# MB1280.net
KiCad netlist of a schematic drawn in Altium Designer
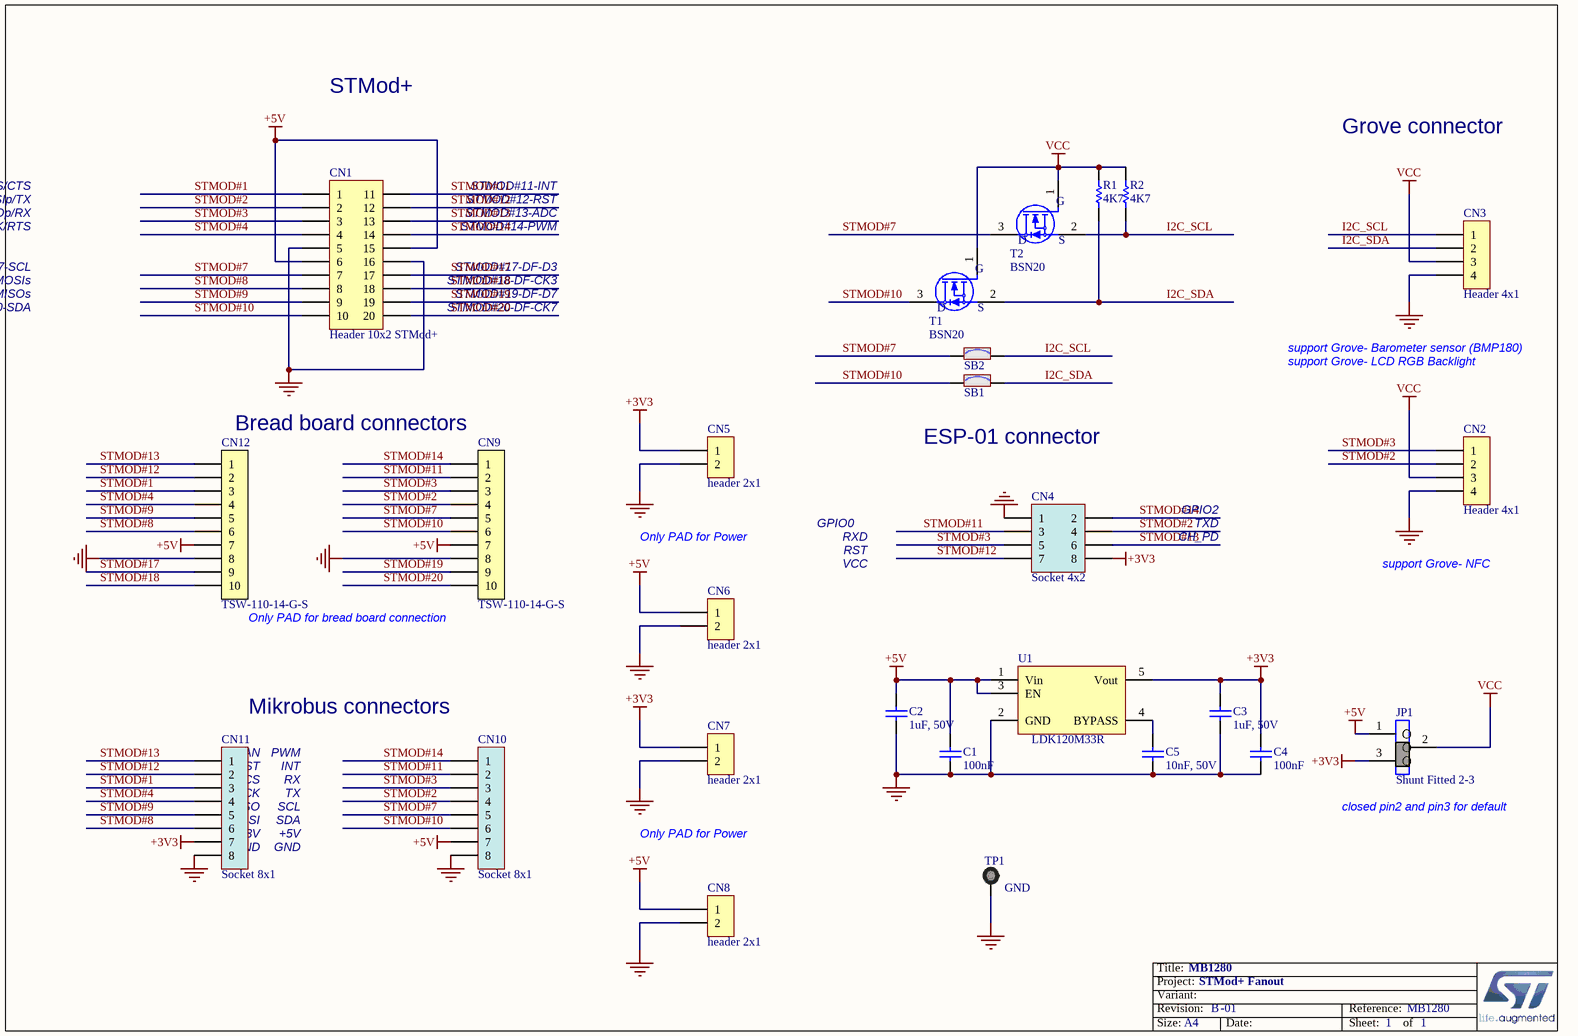
[diagram p0: MB1280.SchDoc]

(export (version "E")
  (design (tool "Eeschema 10.0.6"))
  (components
    (comp (ref "C1")
      (value "100nF")
      (footprint "C0603")
      (description "Capacitor, MLCC, 100nF, 16V, X7R, 10%, 0603, T=0,8mm")
      (fields
        (field (name "INTERNAL_PART_NUMBER") "MCD-00211")
        (field (name "MANUFACTURER_PART_NUMBER") "CC0603KRX7R7BB104")
        (field (name "PROVIDED_BY") "SUBCO")
      )
      (libsource (lib "MCD_PARTS_database") (part "Capacitor"))
    )
    (comp (ref "C2")
      (value "1uF, 50V")
      (footprint "C0603_H0P8")
      (description "Capacitor,1uF,50V,X5R,10%,0603, T=0.8mm")
      (fields
        (field (name "INTERNAL_PART_NUMBER") "MCD-01703")
        (field (name "MANUFACTURER_PART_NUMBER") "CC0603KRX5R9BB105")
        (field (name "PROVIDED_BY") "SUBCO")
      )
      (libsource (lib "MCD_PARTS_database") (part "Capacitor"))
    )
    (comp (ref "C3")
      (value "1uF, 50V")
      (footprint "C0603_H0P8")
      (description "Capacitor,1uF,50V,X5R,10%,0603, T=0.8mm")
      (fields
        (field (name "INTERNAL_PART_NUMBER") "MCD-01703")
        (field (name "MANUFACTURER_PART_NUMBER") "CC0603KRX5R9BB105")
        (field (name "PROVIDED_BY") "SUBCO")
      )
      (libsource (lib "MCD_PARTS_database") (part "Capacitor"))
    )
    (comp (ref "C4")
      (value "100nF")
      (footprint "C0603")
      (description "Capacitor, MLCC, 100nF, 16V, X7R, 10%, 0603, T=0,8mm")
      (fields
        (field (name "INTERNAL_PART_NUMBER") "MCD-00211")
        (field (name "MANUFACTURER_PART_NUMBER") "CC0603KRX7R7BB104")
        (field (name "PROVIDED_BY") "SUBCO")
      )
      (libsource (lib "MCD_PARTS_database") (part "Capacitor"))
    )
    (comp (ref "C5")
      (value "10nF, 50V")
      (footprint "C0603")
      (description "Capacitor,10nF,50V,X7R,10%,0603")
      (fields
        (field (name "INTERNAL_PART_NUMBER") "MCD-01102")
        (field (name "MANUFACTURER_PART_NUMBER") "CC0603KRX7R9BB103")
        (field (name "PROVIDED_BY") "SUBCO")
      )
      (libsource (lib "MCD_PARTS_database") (part "Capacitor"))
    )
    (comp (ref "CN1")
      (value "Header 10x2 STMod+")
      (footprint "CON_SAMTEC_TMM-110-01-L-D-RA__STMOD+")
      (description "Header 10x2, 2mm, RA, TH, Height 3.20mm/3.50mm")
      (fields
        (field (name "INTERNAL_PART_NUMBER") "MCD-00288")
        (field (name "MANUFACTURER_PART_NUMBER") "TMM-110-01-L-D-RA")
        (field (name "PROVIDED_BY") "SUBCO")
      )
      (libsource (lib "MCD_PARTS_database") (part "Header 10x2 STMod+"))
    )
    (comp (ref "CN2")
      (value "Header 4x1")
      (footprint "CON_988-JIUBABA_A2006LF-04A")
      (description "Header 4x1, 2mm, VR, SMT")
      (fields
        (field (name "INTERNAL_PART_NUMBER") "MCD-01741")
        (field (name "MANUFACTURER_PART_NUMBER") "A2006LF-04A")
        (field (name "PROVIDED_BY") "SUBCO")
      )
      (libsource (lib "MCD_PARTS_database") (part "Header 4x1"))
    )
    (comp (ref "CN3")
      (value "Header 4x1")
      (footprint "CON_988-JIUBABA_A2006LF-04A")
      (description "Header 4x1, 2mm, VR, SMT")
      (fields
        (field (name "INTERNAL_PART_NUMBER") "MCD-01741")
        (field (name "MANUFACTURER_PART_NUMBER") "A2006LF-04A")
        (field (name "PROVIDED_BY") "SUBCO")
      )
      (libsource (lib "MCD_PARTS_database") (part "Header 4x1"))
    )
    (comp (ref "CN4")
      (value "Socket 4x2")
      (footprint "CON_SAMTEC_SSW-104-01-X-D")
      (description "Socket 4x2,2.54mm,VR,TH, height 8.51/2.64mm")
      (fields
        (field (name "INTERNAL_PART_NUMBER") "MCD-01742")
        (field (name "MANUFACTURER_PART_NUMBER") "SSW-104-01-G-D")
        (field (name "PROVIDED_BY") "SUBCO")
      )
      (libsource (lib "MCD_PARTS_database") (part "Socket 4x2"))
    )
    (comp (ref "CN5")
      (value "header 2x1")
      (footprint "CON_988-JIUBABA_PHFS25-11-02-G0B115-T-1")
      (description "Header, 2x1, 2.54mm, VR, TH, Height 6mm/3mm")
      (fields
        (field (name "INTERNAL_PART_NUMBER") "MCD-00314")
        (field (name "MANUFACTURER_PART_NUMBER") "PHFS25-11-02-G0B115-T-1")
        (field (name "PROVIDED_BY") "SUBCO")
      )
      (libsource (lib "MCD_PARTS_database") (part "Header 2x1"))
    )
    (comp (ref "CN6")
      (value "header 2x1")
      (footprint "CON_988-JIUBABA_PHFS25-11-02-G0B115-T-1")
      (description "Header, 2x1, 2.54mm, VR, TH, Height 6mm/3mm")
      (fields
        (field (name "INTERNAL_PART_NUMBER") "MCD-00314")
        (field (name "MANUFACTURER_PART_NUMBER") "PHFS25-11-02-G0B115-T-1")
        (field (name "PROVIDED_BY") "SUBCO")
      )
      (libsource (lib "MCD_PARTS_database") (part "Header 2x1"))
    )
    (comp (ref "CN7")
      (value "header 2x1")
      (footprint "CON_988-JIUBABA_PHFS25-11-02-G0B115-T-1")
      (description "Header, 2x1, 2.54mm, VR, TH, Height 6mm/3mm")
      (fields
        (field (name "INTERNAL_PART_NUMBER") "MCD-00314")
        (field (name "MANUFACTURER_PART_NUMBER") "PHFS25-11-02-G0B115-T-1")
        (field (name "PROVIDED_BY") "SUBCO")
      )
      (libsource (lib "MCD_PARTS_database") (part "Header 2x1"))
    )
    (comp (ref "CN8")
      (value "header 2x1")
      (footprint "CON_988-JIUBABA_PHFS25-11-02-G0B115-T-1")
      (description "Header, 2x1, 2.54mm, VR, TH, Height 6mm/3mm")
      (fields
        (field (name "INTERNAL_PART_NUMBER") "MCD-00314")
        (field (name "MANUFACTURER_PART_NUMBER") "PHFS25-11-02-G0B115-T-1")
        (field (name "PROVIDED_BY") "SUBCO")
      )
      (libsource (lib "MCD_PARTS_database") (part "Header 2x1"))
    )
    (comp (ref "CN9")
      (value "TSW-110-14-G-S")
      (footprint "CON_SAMTEC_TSW-110-14-G-S")
      (description "Header 10x1, 2,54mm height  10.67mm")
      (fields
        (field (name "INTERNAL_PART_NUMBER") "MCD-01591")
        (field (name "MANUFACTURER") "SAMTEC")
        (field (name "PROVIDED_BY") "SUBCO")
      )
      (libsource (lib "MCD_PARTS_database") (part "Header 10x1"))
    )
    (comp (ref "CN10")
      (value "Socket 8x1")
      (footprint "CON_SAMTEC_SSW-108-01-X-S")
      (description "Socket 8x1, 2.54mm, VR, TH, height 8.51/2.64mm")
      (fields
        (field (name "INTERNAL_PART_NUMBER") "MCD-01743")
        (field (name "MANUFACTURER_PART_NUMBER") "SSW-108-01-x-S")
        (field (name "PROVIDED_BY") "SUBCO")
      )
      (libsource (lib "MCD_PARTS_database") (part "Socket 8x1"))
    )
    (comp (ref "CN11")
      (value "Socket 8x1")
      (footprint "CON_SAMTEC_SSW-108-01-X-S")
      (description "Socket 8x1, 2.54mm, VR, TH, height 8.51/2.64mm")
      (fields
        (field (name "INTERNAL_PART_NUMBER") "MCD-01743")
        (field (name "MANUFACTURER_PART_NUMBER") "SSW-108-01-x-S")
        (field (name "PROVIDED_BY") "SUBCO")
      )
      (libsource (lib "MCD_PARTS_database") (part "Socket 8x1"))
    )
    (comp (ref "CN12")
      (value "TSW-110-14-G-S")
      (footprint "CON_SAMTEC_TSW-110-14-G-S")
      (description "Header 10x1, 2,54mm height  10.67mm")
      (fields
        (field (name "INTERNAL_PART_NUMBER") "MCD-01591")
        (field (name "MANUFACTURER") "SAMTEC")
        (field (name "PROVIDED_BY") "SUBCO")
      )
      (libsource (lib "MCD_PARTS_database") (part "Header 10x1"))
    )
    (comp (ref "JP1")
      (value "Shunt Fitted 2-3")
      (footprint "CON_SAMTEC_TSW-103-07-F-S")
      (description "Header, 3x1, 2,54mm, VR, TH, Height 5.84mm/2.54mm - Shunt Fitted 2-3 by default")
      (fields
        (field (name "INTERNAL_PART_NUMBER") "MCD-00685")
        (field (name "MANUFACTURER_PART_NUMBER") "TSW-103-07-F-S")
        (field (name "PROVIDED_BY") "SUBCO")
      )
      (libsource (lib "MCD_PARTS_database") (part "Jumper_Header 3x1 Fitted 2-3"))
    )
    (comp (ref "R1")
      (value "4K7")
      (footprint "R0603")
      (description "Resistor,4K7,0603,1%,1/10W")
      (fields
        (field (name "INTERNAL_PART_NUMBER") "MCD-00219")
        (field (name "MANUFACTURER_PART_NUMBER") "RC0603FR-074K7L")
        (field (name "PROVIDED_BY") "SUBCO")
      )
      (libsource (lib "MCD_PARTS_database") (part "Resistor"))
    )
    (comp (ref "R2")
      (value "4K7")
      (footprint "R0603")
      (description "Resistor,4K7,0603,1%,1/10W")
      (fields
        (field (name "INTERNAL_PART_NUMBER") "MCD-00219")
        (field (name "MANUFACTURER_PART_NUMBER") "RC0603FR-074K7L")
        (field (name "PROVIDED_BY") "SUBCO")
      )
      (libsource (lib "MCD_PARTS_database") (part "Resistor"))
    )
    (comp (ref "SB1")
      (value "SB_ON")
      (footprint "SOLDER-BRIDGE_R0603-0R")
      (description "Solder Bridge ON")
      (fields
        (field (name "INTERNAL_PART_NUMBER") "MCD-00071")
        (field (name "MANUFACTURER_PART_NUMBER") "RC0603JR-070RL")
        (field (name "PROVIDED_BY") "SUBCO")
      )
      (libsource (lib "MCD_PARTS_database") (part "SB_ON"))
    )
    (comp (ref "SB2")
      (value "SB_ON")
      (footprint "SOLDER-BRIDGE_R0603-0R")
      (description "Solder Bridge ON")
      (fields
        (field (name "INTERNAL_PART_NUMBER") "MCD-00071")
        (field (name "MANUFACTURER_PART_NUMBER") "RC0603JR-070RL")
        (field (name "PROVIDED_BY") "SUBCO")
      )
      (libsource (lib "MCD_PARTS_database") (part "SB_ON"))
    )
    (comp (ref "T1")
      (value "BSN20")
      (footprint "MOS_SOT23")
      (description "N-channel enhancement mode field-effect transistor")
      (fields
        (field (name "INTERNAL_PART_NUMBER") "MCD-00151")
        (field (name "MANUFACTURER") "NXP")
        (field (name "PROVIDED_BY") "SUBCO")
      )
      (libsource (lib "MCD_PARTS_database") (part "BSN20"))
    )
    (comp (ref "T2")
      (value "BSN20")
      (footprint "MOS_SOT23")
      (description "N-channel enhancement mode field-effect transistor")
      (fields
        (field (name "INTERNAL_PART_NUMBER") "MCD-00151")
        (field (name "MANUFACTURER") "NXP")
        (field (name "PROVIDED_BY") "SUBCO")
      )
      (libsource (lib "MCD_PARTS_database") (part "BSN20"))
    )
    (comp (ref "TP1")
      (value "GND")
      (footprint "TP_PTH_1MM_2MM")
      (description "Test Point trought hole 1mm/2mm")
      (fields
        (field (name "INTERNAL_PART_NUMBER") "MCD-01506")
        (field (name "MANUFACTURER_PART_NUMBER") "n/a")
      )
      (libsource (lib "MCD_PARTS_database") (part "Test_Point_PTH_1mm_2mm"))
    )
    (comp (ref "U1")
      (value "LDK120M33R")
      (footprint "REG_SOT23-5L")
      (description "200 mA low quiescent current very low noise LDO")
      (fields
        (field (name "INTERNAL_PART_NUMBER") "MCD-00663")
        (field (name "MANUFACTURER") "STMICROELECTRONICS")
        (field (name "PROVIDED_BY") "SUBCO with ST control")
      )
      (libsource (lib "MCD_PARTS_database") (part "LDK120M33R"))
    )
  )
  (nets
    (net (code "1") (name "+3V3") (class "Default")
      (node (ref "C3") (pin "2") (pinfunction "2_2") (pintype "passive"))
      (node (ref "C4") (pin "2") (pinfunction "2_2") (pintype "passive"))
      (node (ref "CN11") (pin "7") (pinfunction "7_7") (pintype "passive"))
      (node (ref "CN4") (pin "8") (pinfunction "8_8") (pintype "passive"))
      (node (ref "CN5") (pin "1") (pinfunction "1_1") (pintype "passive"))
      (node (ref "CN7") (pin "1") (pinfunction "1_1") (pintype "passive"))
      (node (ref "JP1") (pin "3") (pinfunction "3_3") (pintype "passive"))
      (node (ref "U1") (pin "5") (pinfunction "Vout_5") (pintype "power_in"))
    )
    (net (code "2") (name "+5V") (class "Default")
      (node (ref "C1") (pin "2") (pinfunction "2_2") (pintype "passive"))
      (node (ref "C2") (pin "2") (pinfunction "2_2") (pintype "passive"))
      (node (ref "CN1") (pin "15") (pinfunction "15_15") (pintype "passive"))
      (node (ref "CN1") (pin "6") (pinfunction "6_6") (pintype "passive"))
      (node (ref "CN10") (pin "7") (pinfunction "7_7") (pintype "passive"))
      (node (ref "CN12") (pin "7") (pinfunction "7_7") (pintype "passive"))
      (node (ref "CN6") (pin "1") (pinfunction "1_1") (pintype "passive"))
      (node (ref "CN8") (pin "1") (pinfunction "1_1") (pintype "passive"))
      (node (ref "CN9") (pin "7") (pinfunction "7_7") (pintype "passive"))
      (node (ref "JP1") (pin "1") (pinfunction "1_1") (pintype "passive"))
      (node (ref "U1") (pin "1") (pinfunction "Vin_1") (pintype "power_in"))
      (node (ref "U1") (pin "3") (pinfunction "EN_3") (pintype "passive"))
    )
    (net (code "3") (name "/I2C_SCL") (class "Default")
      (node (ref "CN3") (pin "1") (pinfunction "1_1") (pintype "passive"))
      (node (ref "R2") (pin "2") (pinfunction "2_2") (pintype "passive"))
      (node (ref "SB2") (pin "2") (pinfunction "2_2") (pintype "passive"))
      (node (ref "T2") (pin "2") (pinfunction "S_2") (pintype "passive"))
    )
    (net (code "4") (name "/I2C_SDA") (class "Default")
      (node (ref "CN3") (pin "2") (pinfunction "2_2") (pintype "passive"))
      (node (ref "R1") (pin "2") (pinfunction "2_2") (pintype "passive"))
      (node (ref "SB1") (pin "2") (pinfunction "2_2") (pintype "passive"))
      (node (ref "T1") (pin "2") (pinfunction "S_2") (pintype "passive"))
    )
    (net (code "5") (name "/STMOD#1") (class "Default")
      (node (ref "CN1") (pin "1") (pinfunction "1_1") (pintype "passive"))
      (node (ref "CN11") (pin "3") (pinfunction "3_3") (pintype "passive"))
      (node (ref "CN12") (pin "3") (pinfunction "3_3") (pintype "passive"))
    )
    (net (code "6") (name "/STMOD#2") (class "Default")
      (node (ref "CN1") (pin "2") (pinfunction "2_2") (pintype "passive"))
      (node (ref "CN10") (pin "4") (pinfunction "4_4") (pintype "passive"))
      (node (ref "CN2") (pin "2") (pinfunction "2_2") (pintype "passive"))
      (node (ref "CN4") (pin "4") (pinfunction "4_4") (pintype "passive"))
      (node (ref "CN9") (pin "4") (pinfunction "4_4") (pintype "passive"))
    )
    (net (code "7") (name "/STMOD#3") (class "Default")
      (node (ref "CN1") (pin "3") (pinfunction "3_3") (pintype "passive"))
      (node (ref "CN10") (pin "3") (pinfunction "3_3") (pintype "passive"))
      (node (ref "CN2") (pin "1") (pinfunction "1_1") (pintype "passive"))
      (node (ref "CN4") (pin "5") (pinfunction "5_5") (pintype "passive"))
      (node (ref "CN9") (pin "3") (pinfunction "3_3") (pintype "passive"))
    )
    (net (code "8") (name "/STMOD#4") (class "Default")
      (node (ref "CN1") (pin "4") (pinfunction "4_4") (pintype "passive"))
      (node (ref "CN11") (pin "4") (pinfunction "4_4") (pintype "passive"))
      (node (ref "CN12") (pin "4") (pinfunction "4_4") (pintype "passive"))
    )
    (net (code "9") (name "/STMOD#7") (class "Default")
      (node (ref "CN1") (pin "7") (pinfunction "7_7") (pintype "passive"))
      (node (ref "CN10") (pin "5") (pinfunction "5_5") (pintype "passive"))
      (node (ref "CN9") (pin "5") (pinfunction "5_5") (pintype "passive"))
      (node (ref "SB2") (pin "1") (pinfunction "1_1") (pintype "passive"))
      (node (ref "T2") (pin "3") (pinfunction "D_3") (pintype "passive"))
    )
    (net (code "10") (name "/STMOD#8") (class "Default")
      (node (ref "CN1") (pin "8") (pinfunction "8_8") (pintype "passive"))
      (node (ref "CN11") (pin "6") (pinfunction "6_6") (pintype "passive"))
      (node (ref "CN12") (pin "6") (pinfunction "6_6") (pintype "passive"))
    )
    (net (code "11") (name "/STMOD#9") (class "Default")
      (node (ref "CN1") (pin "9") (pinfunction "9_9") (pintype "passive"))
      (node (ref "CN11") (pin "5") (pinfunction "5_5") (pintype "passive"))
      (node (ref "CN12") (pin "5") (pinfunction "5_5") (pintype "passive"))
    )
    (net (code "12") (name "/STMOD#10") (class "Default")
      (node (ref "CN1") (pin "10") (pinfunction "10_10") (pintype "passive"))
      (node (ref "CN10") (pin "6") (pinfunction "6_6") (pintype "passive"))
      (node (ref "CN9") (pin "6") (pinfunction "6_6") (pintype "passive"))
      (node (ref "SB1") (pin "1") (pinfunction "1_1") (pintype "passive"))
      (node (ref "T1") (pin "3") (pinfunction "D_3") (pintype "passive"))
    )
    (net (code "13") (name "/STMOD#11") (class "Default")
      (node (ref "CN1") (pin "11") (pinfunction "11_11") (pintype "passive"))
      (node (ref "CN10") (pin "2") (pinfunction "2_2") (pintype "passive"))
      (node (ref "CN4") (pin "3") (pinfunction "3_3") (pintype "passive"))
      (node (ref "CN9") (pin "2") (pinfunction "2_2") (pintype "passive"))
    )
    (net (code "14") (name "/STMOD#12") (class "Default")
      (node (ref "CN1") (pin "12") (pinfunction "12_12") (pintype "passive"))
      (node (ref "CN11") (pin "2") (pinfunction "2_2") (pintype "passive"))
      (node (ref "CN12") (pin "2") (pinfunction "2_2") (pintype "passive"))
      (node (ref "CN4") (pin "7") (pinfunction "7_7") (pintype "passive"))
    )
    (net (code "15") (name "/STMOD#13") (class "Default")
      (node (ref "CN1") (pin "13") (pinfunction "13_13") (pintype "passive"))
      (node (ref "CN11") (pin "1") (pinfunction "1_1") (pintype "passive"))
      (node (ref "CN12") (pin "1") (pinfunction "1_1") (pintype "passive"))
      (node (ref "CN4") (pin "6") (pinfunction "6_6") (pintype "passive"))
    )
    (net (code "16") (name "/STMOD#14") (class "Default")
      (node (ref "CN1") (pin "14") (pinfunction "14_14") (pintype "passive"))
      (node (ref "CN10") (pin "1") (pinfunction "1_1") (pintype "passive"))
      (node (ref "CN4") (pin "2") (pinfunction "2_2") (pintype "passive"))
      (node (ref "CN9") (pin "1") (pinfunction "1_1") (pintype "passive"))
    )
    (net (code "17") (name "/STMOD#17") (class "Default")
      (node (ref "CN1") (pin "17") (pinfunction "17_17") (pintype "passive"))
      (node (ref "CN12") (pin "9") (pinfunction "9_9") (pintype "passive"))
    )
    (net (code "18") (name "/STMOD#18") (class "Default")
      (node (ref "CN1") (pin "18") (pinfunction "18_18") (pintype "passive"))
      (node (ref "CN12") (pin "10") (pinfunction "10_10") (pintype "passive"))
    )
    (net (code "19") (name "/STMOD#19") (class "Default")
      (node (ref "CN1") (pin "19") (pinfunction "19_19") (pintype "passive"))
      (node (ref "CN9") (pin "9") (pinfunction "9_9") (pintype "passive"))
    )
    (net (code "20") (name "/STMOD#20") (class "Default")
      (node (ref "CN1") (pin "20") (pinfunction "20_20") (pintype "passive"))
      (node (ref "CN9") (pin "10") (pinfunction "10_10") (pintype "passive"))
    )
    (net (code "21") (name "GND") (class "Default")
      (node (ref "C1") (pin "1") (pinfunction "1_1") (pintype "passive"))
      (node (ref "C2") (pin "1") (pinfunction "1_1") (pintype "passive"))
      (node (ref "C3") (pin "1") (pinfunction "1_1") (pintype "passive"))
      (node (ref "C4") (pin "1") (pinfunction "1_1") (pintype "passive"))
      (node (ref "C5") (pin "1") (pinfunction "1_1") (pintype "passive"))
      (node (ref "CN1") (pin "16") (pinfunction "16_16") (pintype "passive"))
      (node (ref "CN1") (pin "5") (pinfunction "5_5") (pintype "passive"))
      (node (ref "CN10") (pin "8") (pinfunction "8_8") (pintype "passive"))
      (node (ref "CN11") (pin "8") (pinfunction "8_8") (pintype "passive"))
      (node (ref "CN12") (pin "8") (pinfunction "8_8") (pintype "passive"))
      (node (ref "CN2") (pin "4") (pinfunction "4_4") (pintype "passive"))
      (node (ref "CN3") (pin "4") (pinfunction "4_4") (pintype "passive"))
      (node (ref "CN4") (pin "1") (pinfunction "1_1") (pintype "passive"))
      (node (ref "CN5") (pin "2") (pinfunction "2_2") (pintype "passive"))
      (node (ref "CN6") (pin "2") (pinfunction "2_2") (pintype "passive"))
      (node (ref "CN7") (pin "2") (pinfunction "2_2") (pintype "passive"))
      (node (ref "CN8") (pin "2") (pinfunction "2_2") (pintype "passive"))
      (node (ref "CN9") (pin "8") (pinfunction "8_8") (pintype "passive"))
      (node (ref "TP1") (pin "1") (pinfunction "1_1") (pintype "passive"))
      (node (ref "U1") (pin "2") (pinfunction "GND_2") (pintype "passive"))
    )
    (net (code "22") (name "Net-(U1-BYPASS)") (class "Default")
      (node (ref "C5") (pin "2") (pinfunction "2_2") (pintype "passive"))
      (node (ref "U1") (pin "4") (pinfunction "BYPASS_4") (pintype "passive"))
    )
    (net (code "23") (name "VCC") (class "Default")
      (node (ref "CN2") (pin "3") (pinfunction "3_3") (pintype "passive"))
      (node (ref "CN3") (pin "3") (pinfunction "3_3") (pintype "passive"))
      (node (ref "JP1") (pin "2") (pinfunction "2_2") (pintype "passive"))
      (node (ref "R1") (pin "1") (pinfunction "1_1") (pintype "passive"))
      (node (ref "R2") (pin "1") (pinfunction "1_1") (pintype "passive"))
      (node (ref "T1") (pin "1") (pinfunction "G_1") (pintype "passive"))
      (node (ref "T2") (pin "1") (pinfunction "G_1") (pintype "passive"))
    )
  )
)
